# v2-DCSupplyHub-current.net
KiCad netlist of a schematic drawn in Altium Designer
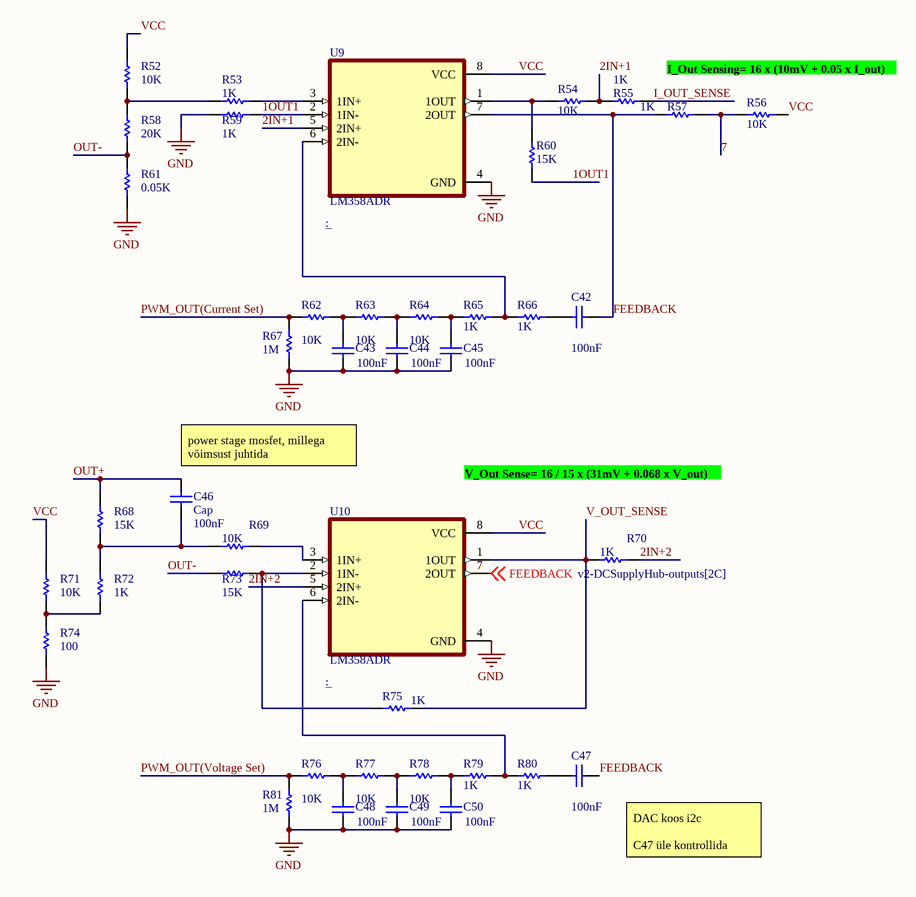
[diagram p0: v2-DCSupplyHub-current.SchDoc]

(export (version "E")
  (design (tool "Eeschema 10.0.6"))
  (components
    (comp (ref "C42")
      (value "100nF")
      (footprint "CAPC3216X110N")
      (description "Capacitor")
      (fields (field (name "Comment") "Cap") (field (name "PUBLISHER") "Altium Limited"))
      (libsource (lib "cc cv power supply") (part "Cap"))
    )
    (comp (ref "C43")
      (value "100nF")
      (footprint "CAPC3216X110N")
      (description "Capacitor")
      (fields (field (name "Comment") "Cap") (field (name "PUBLISHER") "Altium Limited"))
      (libsource (lib "cc cv power supply") (part "Cap"))
    )
    (comp (ref "C44")
      (value "100nF")
      (footprint "CAPC3216X110N")
      (description "Capacitor")
      (fields (field (name "Comment") "Cap") (field (name "PUBLISHER") "Altium Limited"))
      (libsource (lib "cc cv power supply") (part "Cap"))
    )
    (comp (ref "C45")
      (value "100nF")
      (footprint "CAPC3216X110N")
      (description "Capacitor")
      (fields (field (name "Comment") "Cap") (field (name "PUBLISHER") "Altium Limited"))
      (libsource (lib "cc cv power supply") (part "Cap"))
    )
    (comp (ref "C46")
      (value "Cap")
      (footprint "CAPC3216X110N")
      (description "Capacitor")
      (fields (field (name "ALTIUM_VALUE") "100nF") (field (name "PUBLISHER") "Altium Limited"))
      (libsource (lib "cc cv power supply") (part "Cap"))
    )
    (comp (ref "C47")
      (value "100nF")
      (footprint "CAPC3216X110N")
      (description "Capacitor")
      (fields (field (name "Comment") "Cap") (field (name "PUBLISHER") "Altium Limited"))
      (libsource (lib "cc cv power supply") (part "Cap"))
    )
    (comp (ref "C48")
      (value "100nF")
      (footprint "CAPC3216X110N")
      (description "Capacitor")
      (fields (field (name "Comment") "Cap") (field (name "PUBLISHER") "Altium Limited"))
      (libsource (lib "cc cv power supply") (part "Cap"))
    )
    (comp (ref "C49")
      (value "100nF")
      (footprint "CAPC3216X110N")
      (description "Capacitor")
      (fields (field (name "Comment") "Cap") (field (name "PUBLISHER") "Altium Limited"))
      (libsource (lib "cc cv power supply") (part "Cap"))
    )
    (comp (ref "C50")
      (value "100nF")
      (footprint "CAPC3216X110N")
      (description "Capacitor")
      (fields (field (name "Comment") "Cap") (field (name "PUBLISHER") "Altium Limited"))
      (libsource (lib "cc cv power supply") (part "Cap"))
    )
    (comp (ref "R52")
      (value "10K")
      (footprint "RESC3116X60N")
      (description "Resistor")
      (fields (field (name "Comment") "Res1") (field (name "PUBLISHER") "Altium Limited"))
      (libsource (lib "cc cv power supply") (part "Res1"))
    )
    (comp (ref "R53")
      (value "1K")
      (footprint "RESC3116X60N")
      (description "Resistor")
      (fields (field (name "Comment") "Res1") (field (name "PUBLISHER") "Altium Limited"))
      (libsource (lib "cc cv power supply") (part "Res1"))
    )
    (comp (ref "R54")
      (value "10K")
      (footprint "RESC3116X60N")
      (description "Resistor")
      (fields (field (name "Comment") "Res1") (field (name "PUBLISHER") "Altium Limited"))
      (libsource (lib "cc cv power supply") (part "Res1"))
    )
    (comp (ref "R55")
      (value "1K")
      (footprint "RESC3116X60N")
      (description "Resistor")
      (fields (field (name "Comment") "Res1") (field (name "PUBLISHER") "Altium Limited"))
      (libsource (lib "cc cv power supply") (part "Res1"))
    )
    (comp (ref "R56")
      (value "10K")
      (footprint "RESC3116X60N")
      (description "Resistor")
      (fields (field (name "Comment") "Res1") (field (name "PUBLISHER") "Altium Limited"))
      (libsource (lib "cc cv power supply") (part "Res1"))
    )
    (comp (ref "R57")
      (value "1K")
      (footprint "RESC3116X60N")
      (description "Resistor")
      (fields (field (name "Comment") "Res1") (field (name "PUBLISHER") "Altium Limited"))
      (libsource (lib "cc cv power supply") (part "Res1"))
    )
    (comp (ref "R58")
      (value "20K")
      (footprint "RESC3116X60N")
      (description "Resistor")
      (fields (field (name "Comment") "Res1") (field (name "PUBLISHER") "Altium Limited"))
      (libsource (lib "cc cv power supply") (part "Res1"))
    )
    (comp (ref "R59")
      (value "1K")
      (footprint "RESC3116X60N")
      (description "Resistor")
      (fields (field (name "Comment") "Res1") (field (name "PUBLISHER") "Altium Limited"))
      (libsource (lib "cc cv power supply") (part "Res1"))
    )
    (comp (ref "R60")
      (value "15K")
      (footprint "RESC3116X60N")
      (description "Resistor")
      (fields (field (name "Comment") "Res1") (field (name "PUBLISHER") "Altium Limited"))
      (libsource (lib "cc cv power supply") (part "Res1"))
    )
    (comp (ref "R61")
      (value "0.05K")
      (footprint "RESC3116X60N")
      (description "Resistor")
      (fields (field (name "Comment") "Res1") (field (name "PUBLISHER") "Altium Limited"))
      (libsource (lib "cc cv power supply") (part "Res1"))
    )
    (comp (ref "R62")
      (value "10K")
      (footprint "RESC3116X60N")
      (description "Resistor")
      (fields (field (name "Comment") "Res1") (field (name "PUBLISHER") "Altium Limited"))
      (libsource (lib "cc cv power supply") (part "Res1"))
    )
    (comp (ref "R63")
      (value "10K")
      (footprint "RESC3116X60N")
      (description "Resistor")
      (fields (field (name "Comment") "Res1") (field (name "PUBLISHER") "Altium Limited"))
      (libsource (lib "cc cv power supply") (part "Res1"))
    )
    (comp (ref "R64")
      (value "10K")
      (footprint "RESC3116X60N")
      (description "Resistor")
      (fields (field (name "Comment") "Res1") (field (name "PUBLISHER") "Altium Limited"))
      (libsource (lib "cc cv power supply") (part "Res1"))
    )
    (comp (ref "R65")
      (value "1K")
      (footprint "RESC3116X60N")
      (description "Resistor")
      (fields (field (name "Comment") "Res1") (field (name "PUBLISHER") "Altium Limited"))
      (libsource (lib "cc cv power supply") (part "Res1"))
    )
    (comp (ref "R66")
      (value "1K")
      (footprint "RESC3116X60N")
      (description "Resistor")
      (fields (field (name "Comment") "Res1") (field (name "PUBLISHER") "Altium Limited"))
      (libsource (lib "cc cv power supply") (part "Res1"))
    )
    (comp (ref "R67")
      (value "1M")
      (footprint "RESC3116X60N")
      (description "Resistor")
      (fields (field (name "Comment") "Res1") (field (name "PUBLISHER") "Altium Limited"))
      (libsource (lib "cc cv power supply") (part "Res1"))
    )
    (comp (ref "R68")
      (value "15K")
      (footprint "RESC3116X60N")
      (description "Resistor")
      (fields (field (name "Comment") "Res1") (field (name "PUBLISHER") "Altium Limited"))
      (libsource (lib "cc cv power supply") (part "Res1"))
    )
    (comp (ref "R69")
      (value "10K")
      (footprint "RESC3116X60N")
      (description "Resistor")
      (fields (field (name "Comment") "Res1") (field (name "PUBLISHER") "Altium Limited"))
      (libsource (lib "cc cv power supply") (part "Res1"))
    )
    (comp (ref "R70")
      (value "1K")
      (footprint "RESC3116X60N")
      (description "Resistor")
      (fields (field (name "Comment") "Res1") (field (name "PUBLISHER") "Altium Limited"))
      (libsource (lib "cc cv power supply") (part "Res1"))
    )
    (comp (ref "R71")
      (value "10K")
      (footprint "RESC3116X60N")
      (description "Resistor")
      (fields (field (name "Comment") "Res1") (field (name "PUBLISHER") "Altium Limited"))
      (libsource (lib "cc cv power supply") (part "Res1"))
    )
    (comp (ref "R72")
      (value "1K")
      (footprint "RESC3116X60N")
      (description "Resistor")
      (fields (field (name "Comment") "Res1") (field (name "PUBLISHER") "Altium Limited"))
      (libsource (lib "cc cv power supply") (part "Res1"))
    )
    (comp (ref "R73")
      (value "15K")
      (footprint "RESC3116X60N")
      (description "Resistor")
      (fields (field (name "Comment") "Res1") (field (name "PUBLISHER") "Altium Limited"))
      (libsource (lib "cc cv power supply") (part "Res1"))
    )
    (comp (ref "R74")
      (value "100")
      (footprint "RESC3116X60N")
      (description "Resistor")
      (fields (field (name "Comment") "Res1") (field (name "PUBLISHER") "Altium Limited"))
      (libsource (lib "cc cv power supply") (part "Res1"))
    )
    (comp (ref "R75")
      (value "1K")
      (footprint "RESC3116X60N")
      (description "Resistor")
      (fields (field (name "Comment") "Res1") (field (name "PUBLISHER") "Altium Limited"))
      (libsource (lib "cc cv power supply") (part "Res1"))
    )
    (comp (ref "R76")
      (value "10K")
      (footprint "RESC3116X60N")
      (description "Resistor")
      (fields (field (name "Comment") "Res1") (field (name "PUBLISHER") "Altium Limited"))
      (libsource (lib "cc cv power supply") (part "Res1"))
    )
    (comp (ref "R77")
      (value "10K")
      (footprint "RESC3116X60N")
      (description "Resistor")
      (fields (field (name "Comment") "Res1") (field (name "PUBLISHER") "Altium Limited"))
      (libsource (lib "cc cv power supply") (part "Res1"))
    )
    (comp (ref "R78")
      (value "10K")
      (footprint "RESC3116X60N")
      (description "Resistor")
      (fields (field (name "Comment") "Res1") (field (name "PUBLISHER") "Altium Limited"))
      (libsource (lib "cc cv power supply") (part "Res1"))
    )
    (comp (ref "R79")
      (value "1K")
      (footprint "RESC3116X60N")
      (description "Resistor")
      (fields (field (name "Comment") "Res1") (field (name "PUBLISHER") "Altium Limited"))
      (libsource (lib "cc cv power supply") (part "Res1"))
    )
    (comp (ref "R80")
      (value "1K")
      (footprint "RESC3116X60N")
      (description "Resistor")
      (fields (field (name "Comment") "Res1") (field (name "PUBLISHER") "Altium Limited"))
      (libsource (lib "cc cv power supply") (part "Res1"))
    )
    (comp (ref "R81")
      (value "1M")
      (footprint "RESC3116X60N")
      (description "Resistor")
      (fields (field (name "Comment") "Res1") (field (name "PUBLISHER") "Altium Limited"))
      (libsource (lib "cc cv power supply") (part "Res1"))
    )
    (comp (ref "U9")
      (value "LM358ADR")
      (footprint "SOIC127P599X175-8N")
      (description "Dual improved offset, standard operational amplifier<br /> &nbsp; 8-SOIC 0 to 70")
      (fields (field (name "MF") "Texas Instruments"))
      (libsource (lib "cc cv power supply") (part "LM358ADR"))
    )
    (comp (ref "U10")
      (value "LM358ADR")
      (footprint "SOIC127P599X175-8N")
      (description "Dual improved offset, standard operational amplifier<br /> &nbsp; 8-SOIC 0 to 70")
      (fields (field (name "MF") "Texas Instruments"))
      (libsource (lib "cc cv power supply") (part "LM358ADR"))
    )
  )
  (nets
    (net (code "1") (name "/1OUT1") (class "Default")
      (node (ref "R59") (pin "2") (pinfunction "2_2") (pintype "passive"))
      (node (ref "R60") (pin "1") (pinfunction "1_1") (pintype "passive"))
      (node (ref "U9") (pin "2") (pinfunction "1IN-_2") (pintype "input"))
    )
    (net (code "2") (name "/2IN+1") (class "Default")
      (node (ref "R54") (pin "1") (pinfunction "1_1") (pintype "passive"))
      (node (ref "R55") (pin "2") (pinfunction "2_2") (pintype "passive"))
      (node (ref "U9") (pin "5") (pinfunction "2IN+_5") (pintype "input"))
    )
    (net (code "3") (name "/2IN+2") (class "Default")
      (node (ref "R70") (pin "2") (pinfunction "2_2") (pintype "passive"))
      (node (ref "U10") (pin "5") (pinfunction "2IN+_5") (pintype "input"))
    )
    (net (code "4") (name "/7") (class "Default")
      (node (ref "R56") (pin "2") (pinfunction "2_2") (pintype "passive"))
      (node (ref "R57") (pin "1") (pinfunction "1_1") (pintype "passive"))
    )
    (net (code "5") (name "/I_OUT_SENSE") (class "Default")
      (node (ref "R55") (pin "1") (pinfunction "1_1") (pintype "passive"))
    )
    (net (code "6") (name "/OUT+") (class "Default")
      (node (ref "C46") (pin "1") (pinfunction "1_1") (pintype "passive"))
      (node (ref "R68") (pin "2") (pinfunction "2_2") (pintype "passive"))
    )
    (net (code "7") (name "/OUT-") (class "Default")
      (node (ref "R58") (pin "1") (pinfunction "1_1") (pintype "passive"))
      (node (ref "R61") (pin "2") (pinfunction "2_2") (pintype "passive"))
      (node (ref "R73") (pin "1") (pinfunction "1_1") (pintype "passive"))
    )
    (net (code "8") (name "/PWM_OUT(Current Set)") (class "Default")
      (node (ref "R62") (pin "2") (pinfunction "2_2") (pintype "passive"))
      (node (ref "R67") (pin "2") (pinfunction "2_2") (pintype "passive"))
    )
    (net (code "9") (name "/PWM_OUT(Voltage Set)") (class "Default")
      (node (ref "R76") (pin "2") (pinfunction "2_2") (pintype "passive"))
      (node (ref "R81") (pin "2") (pinfunction "2_2") (pintype "passive"))
    )
    (net (code "10") (name "/VCC") (class "Default")
      (node (ref "R52") (pin "2") (pinfunction "2_2") (pintype "passive"))
      (node (ref "R56") (pin "1") (pinfunction "1_1") (pintype "passive"))
      (node (ref "R71") (pin "2") (pinfunction "2_2") (pintype "passive"))
      (node (ref "U10") (pin "8") (pinfunction "VCC_8") (pintype "power_in"))
      (node (ref "U9") (pin "8") (pinfunction "VCC_8") (pintype "power_in"))
    )
    (net (code "11") (name "/V_OUT_SENSE") (class "Default")
      (node (ref "R70") (pin "1") (pinfunction "1_1") (pintype "passive"))
      (node (ref "R75") (pin "2") (pinfunction "2_2") (pintype "passive"))
      (node (ref "U10") (pin "1") (pinfunction "1OUT_1") (pintype "output"))
    )
    (net (code "12") (name "FEEDBACK") (class "Default")
      (node (ref "C42") (pin "2") (pinfunction "2_2") (pintype "passive"))
      (node (ref "C47") (pin "2") (pinfunction "2_2") (pintype "passive"))
      (node (ref "R57") (pin "2") (pinfunction "2_2") (pintype "passive"))
      (node (ref "U10") (pin "7") (pinfunction "2OUT_7") (pintype "output"))
      (node (ref "U9") (pin "7") (pinfunction "2OUT_7") (pintype "output"))
    )
    (net (code "13") (name "GND") (class "Default")
      (node (ref "C43") (pin "1") (pinfunction "1_1") (pintype "passive"))
      (node (ref "C44") (pin "1") (pinfunction "1_1") (pintype "passive"))
      (node (ref "C45") (pin "1") (pinfunction "1_1") (pintype "passive"))
      (node (ref "C48") (pin "1") (pinfunction "1_1") (pintype "passive"))
      (node (ref "C49") (pin "1") (pinfunction "1_1") (pintype "passive"))
      (node (ref "C50") (pin "1") (pinfunction "1_1") (pintype "passive"))
      (node (ref "R59") (pin "1") (pinfunction "1_1") (pintype "passive"))
      (node (ref "R61") (pin "1") (pinfunction "1_1") (pintype "passive"))
      (node (ref "R67") (pin "1") (pinfunction "1_1") (pintype "passive"))
      (node (ref "R74") (pin "1") (pinfunction "1_1") (pintype "passive"))
      (node (ref "R81") (pin "1") (pinfunction "1_1") (pintype "passive"))
      (node (ref "U10") (pin "4") (pinfunction "GND_4") (pintype "power_in"))
      (node (ref "U9") (pin "4") (pinfunction "GND_4") (pintype "power_in"))
    )
    (net (code "14") (name "Net-(C42-Pad1)") (class "Default")
      (node (ref "C42") (pin "1") (pinfunction "1_1") (pintype "passive"))
      (node (ref "R66") (pin "2") (pinfunction "2_2") (pintype "passive"))
    )
    (net (code "15") (name "Net-(C43-Pad2)") (class "Default")
      (node (ref "C43") (pin "2") (pinfunction "2_2") (pintype "passive"))
      (node (ref "R62") (pin "1") (pinfunction "1_1") (pintype "passive"))
      (node (ref "R63") (pin "2") (pinfunction "2_2") (pintype "passive"))
    )
    (net (code "16") (name "Net-(C44-Pad2)") (class "Default")
      (node (ref "C44") (pin "2") (pinfunction "2_2") (pintype "passive"))
      (node (ref "R63") (pin "1") (pinfunction "1_1") (pintype "passive"))
      (node (ref "R64") (pin "2") (pinfunction "2_2") (pintype "passive"))
    )
    (net (code "17") (name "Net-(C45-Pad2)") (class "Default")
      (node (ref "C45") (pin "2") (pinfunction "2_2") (pintype "passive"))
      (node (ref "R64") (pin "1") (pinfunction "1_1") (pintype "passive"))
      (node (ref "R65") (pin "1") (pinfunction "1_1") (pintype "passive"))
    )
    (net (code "18") (name "Net-(C46-Pad2)") (class "Default")
      (node (ref "C46") (pin "2") (pinfunction "2_2") (pintype "passive"))
      (node (ref "R68") (pin "1") (pinfunction "1_1") (pintype "passive"))
      (node (ref "R69") (pin "1") (pinfunction "1_1") (pintype "passive"))
      (node (ref "R72") (pin "2") (pinfunction "2_2") (pintype "passive"))
    )
    (net (code "19") (name "Net-(C47-Pad1)") (class "Default")
      (node (ref "C47") (pin "1") (pinfunction "1_1") (pintype "passive"))
      (node (ref "R80") (pin "2") (pinfunction "2_2") (pintype "passive"))
    )
    (net (code "20") (name "Net-(C48-Pad2)") (class "Default")
      (node (ref "C48") (pin "2") (pinfunction "2_2") (pintype "passive"))
      (node (ref "R76") (pin "1") (pinfunction "1_1") (pintype "passive"))
      (node (ref "R77") (pin "2") (pinfunction "2_2") (pintype "passive"))
    )
    (net (code "21") (name "Net-(C49-Pad2)") (class "Default")
      (node (ref "C49") (pin "2") (pinfunction "2_2") (pintype "passive"))
      (node (ref "R77") (pin "1") (pinfunction "1_1") (pintype "passive"))
      (node (ref "R78") (pin "2") (pinfunction "2_2") (pintype "passive"))
    )
    (net (code "22") (name "Net-(C50-Pad2)") (class "Default")
      (node (ref "C50") (pin "2") (pinfunction "2_2") (pintype "passive"))
      (node (ref "R78") (pin "1") (pinfunction "1_1") (pintype "passive"))
      (node (ref "R79") (pin "1") (pinfunction "1_1") (pintype "passive"))
    )
    (net (code "23") (name "Net-(R52-Pad1)") (class "Default")
      (node (ref "R52") (pin "1") (pinfunction "1_1") (pintype "passive"))
      (node (ref "R53") (pin "1") (pinfunction "1_1") (pintype "passive"))
      (node (ref "R58") (pin "2") (pinfunction "2_2") (pintype "passive"))
    )
    (net (code "24") (name "Net-(R71-Pad1)") (class "Default")
      (node (ref "R71") (pin "1") (pinfunction "1_1") (pintype "passive"))
      (node (ref "R72") (pin "1") (pinfunction "1_1") (pintype "passive"))
      (node (ref "R74") (pin "2") (pinfunction "2_2") (pintype "passive"))
    )
    (net (code "25") (name "Net-(U9-1IN+)") (class "Default")
      (node (ref "R53") (pin "2") (pinfunction "2_2") (pintype "passive"))
      (node (ref "U9") (pin "3") (pinfunction "1IN+_3") (pintype "input"))
    )
    (net (code "26") (name "Net-(U9-1OUT)") (class "Default")
      (node (ref "R54") (pin "2") (pinfunction "2_2") (pintype "passive"))
      (node (ref "R60") (pin "2") (pinfunction "2_2") (pintype "passive"))
      (node (ref "U9") (pin "1") (pinfunction "1OUT_1") (pintype "output"))
    )
    (net (code "27") (name "Net-(U9-2IN-)") (class "Default")
      (node (ref "R65") (pin "2") (pinfunction "2_2") (pintype "passive"))
      (node (ref "R66") (pin "1") (pinfunction "1_1") (pintype "passive"))
      (node (ref "U9") (pin "6") (pinfunction "2IN-_6") (pintype "input"))
    )
    (net (code "28") (name "Net-(U10-1IN+)") (class "Default")
      (node (ref "R69") (pin "2") (pinfunction "2_2") (pintype "passive"))
      (node (ref "U10") (pin "3") (pinfunction "1IN+_3") (pintype "input"))
    )
    (net (code "29") (name "Net-(U10-1IN-)") (class "Default")
      (node (ref "R73") (pin "2") (pinfunction "2_2") (pintype "passive"))
      (node (ref "R75") (pin "1") (pinfunction "1_1") (pintype "passive"))
      (node (ref "U10") (pin "2") (pinfunction "1IN-_2") (pintype "input"))
    )
    (net (code "30") (name "Net-(U10-2IN-)") (class "Default")
      (node (ref "R79") (pin "2") (pinfunction "2_2") (pintype "passive"))
      (node (ref "R80") (pin "1") (pinfunction "1_1") (pintype "passive"))
      (node (ref "U10") (pin "6") (pinfunction "2IN-_6") (pintype "input"))
    )
  )
)
